# M617X.net
KiCad netlist of a schematic drawn in EAGLE
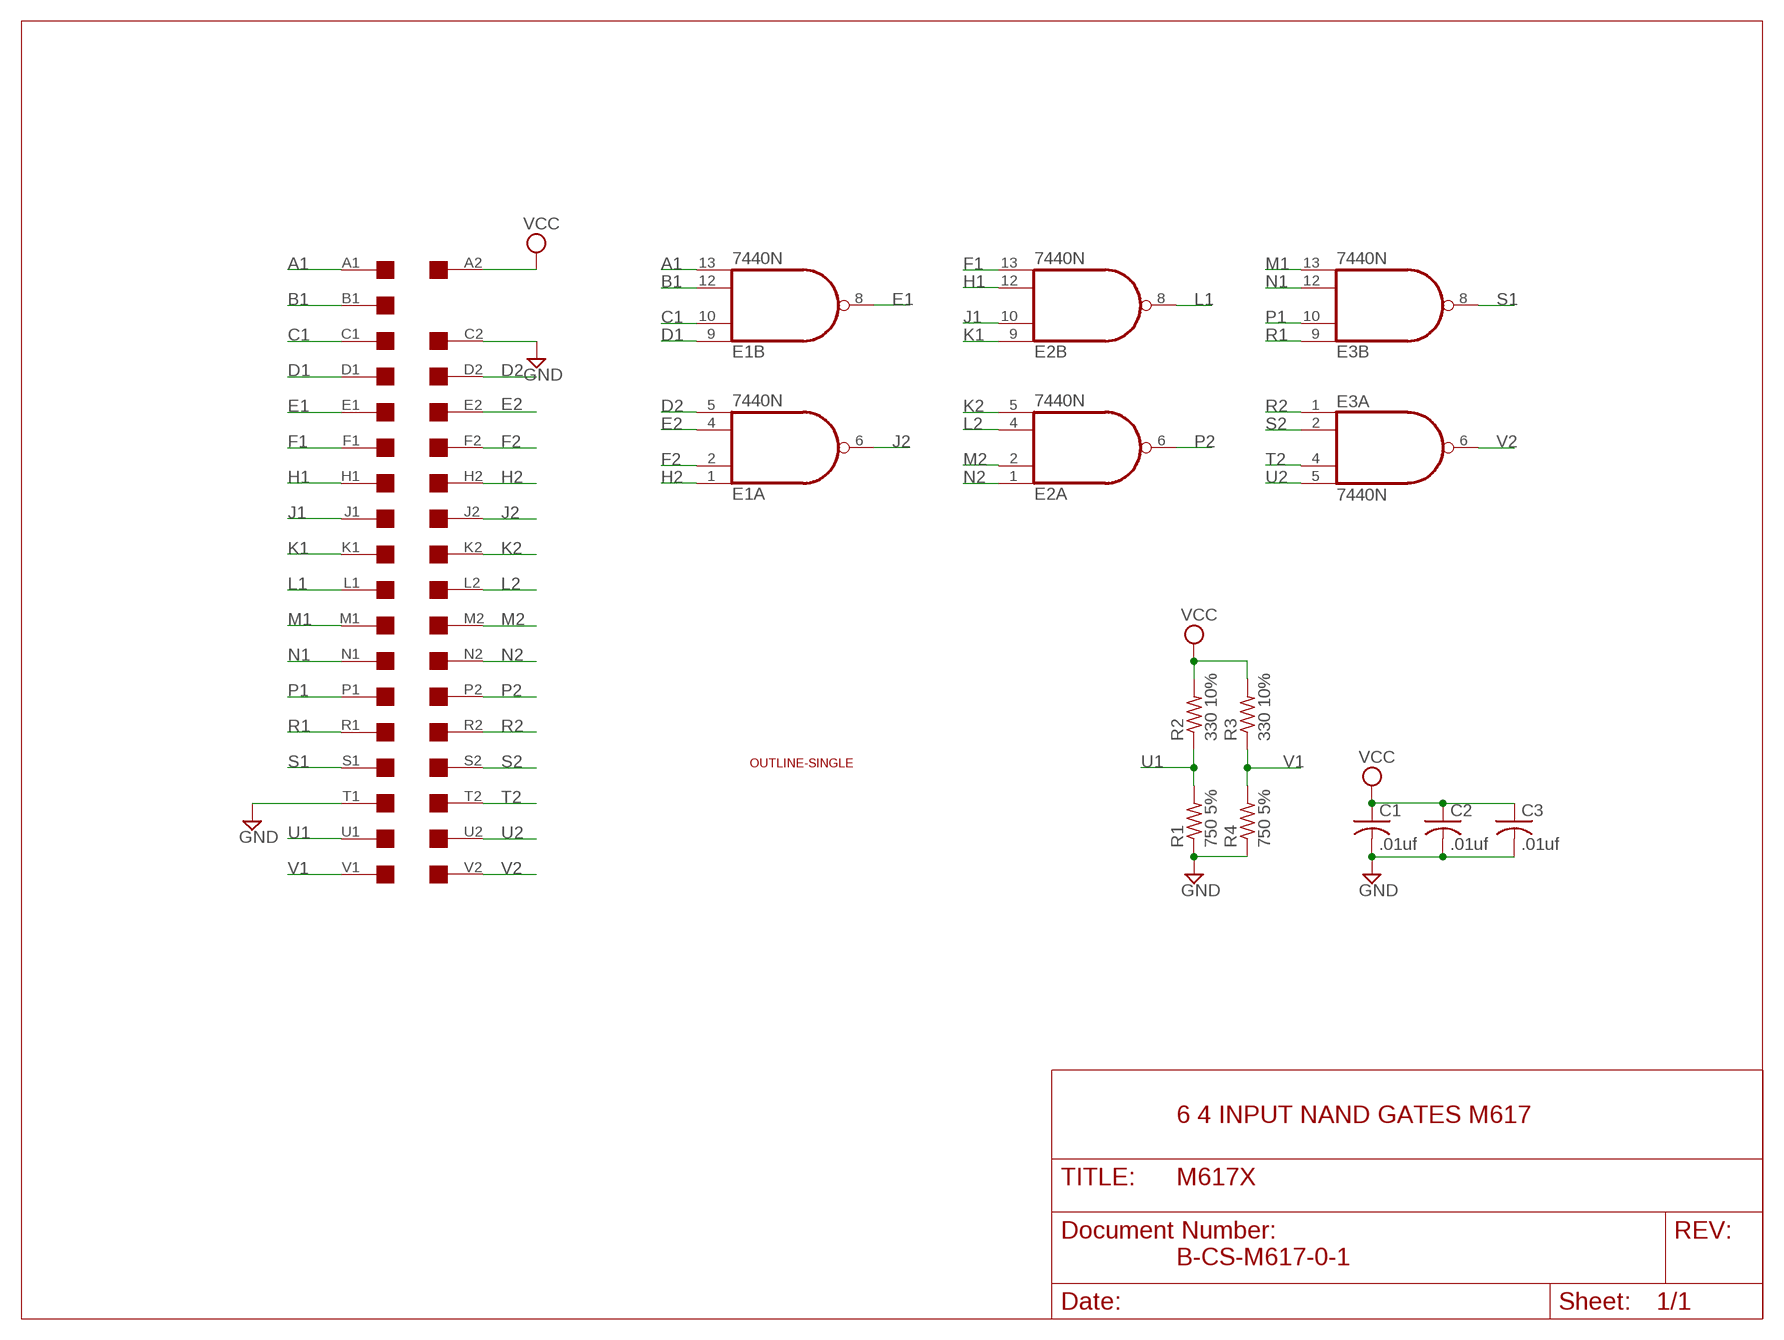
[diagram p0: schematic, sheet 1]

(export (version "E")
  (design (tool "Eeschema 10.0.6"))
  (components
    (comp (ref "C1")
      (value ".01uf")
      (footprint "eagle-import:C050-025X075")
      (libsource (lib "eagle-import") (part "C-US050-025X075"))
    )
    (comp (ref "C2")
      (value ".01uf")
      (footprint "eagle-import:C050-025X075")
      (libsource (lib "eagle-import") (part "C-US050-025X075"))
    )
    (comp (ref "C3")
      (value ".01uf")
      (footprint "eagle-import:C050-025X075")
      (libsource (lib "eagle-import") (part "C-US050-025X075"))
    )
    (comp (ref "E1")
      (value "7440N")
      (footprint "eagle-import:DIL14")
      (libsource (lib "eagle-import") (part "7420NS"))
    )
    (comp (ref "E2")
      (value "7440N")
      (footprint "eagle-import:DIL14")
      (libsource (lib "eagle-import") (part "7420NS"))
    )
    (comp (ref "E3")
      (value "7440N")
      (footprint "eagle-import:DIL14")
      (libsource (lib "eagle-import") (part "7420NS"))
    )
    (comp (ref "R1")
      (value "750 5%")
      (footprint "eagle-import:0207_10")
      (libsource (lib "eagle-import") (part "R-US_0207/10"))
    )
    (comp (ref "R2")
      (value "330 10%")
      (footprint "eagle-import:0207_10")
      (libsource (lib "eagle-import") (part "R-US_0207/10"))
    )
    (comp (ref "R3")
      (value "330 10%")
      (footprint "eagle-import:0207_10")
      (libsource (lib "eagle-import") (part "R-US_0207/10"))
    )
    (comp (ref "R4")
      (value "750 5%")
      (footprint "eagle-import:0207_10")
      (libsource (lib "eagle-import") (part "R-US_0207/10"))
    )
    (comp (ref "U$1")
      (value "SINGLE")
      (footprint "eagle-import:EDGE-CON2")
      (libsource (lib "eagle-import") (part "SINGLE"))
    )
    (comp (ref "U$4")
      (value "OUTLINE-SINGLE")
      (footprint "eagle-import:SINGLE")
      (libsource (lib "eagle-import") (part "OUTLINE-SINGLE"))
    )
  )
  (nets
    (net (code "1") (name "/A1") (class "Default")
      (node (ref "E1") (pin "13") (pinfunction "I3_13") (pintype "input"))
      (node (ref "U$1") (pin "A1") (pinfunction "1_A1") (pintype "bidirectional"))
    )
    (net (code "2") (name "/B1") (class "Default")
      (node (ref "E1") (pin "12") (pinfunction "I2_12") (pintype "input"))
      (node (ref "U$1") (pin "B1") (pinfunction "1_B1") (pintype "bidirectional"))
    )
    (net (code "3") (name "/C1") (class "Default")
      (node (ref "E1") (pin "10") (pinfunction "I1_10") (pintype "input"))
      (node (ref "U$1") (pin "C1") (pinfunction "1_C1") (pintype "bidirectional"))
    )
    (net (code "4") (name "/D1") (class "Default")
      (node (ref "E1") (pin "9") (pinfunction "I0_9") (pintype "input"))
      (node (ref "U$1") (pin "D1") (pinfunction "1_D1") (pintype "bidirectional"))
    )
    (net (code "5") (name "/D2") (class "Default")
      (node (ref "E1") (pin "5") (pinfunction "I3_5") (pintype "input"))
      (node (ref "U$1") (pin "D2") (pinfunction "1_D2") (pintype "bidirectional"))
    )
    (net (code "6") (name "/E1") (class "Default")
      (node (ref "E1") (pin "8") (pinfunction "O_8") (pintype "output"))
      (node (ref "U$1") (pin "E1") (pinfunction "1_E1") (pintype "bidirectional"))
    )
    (net (code "7") (name "/E2") (class "Default")
      (node (ref "E1") (pin "4") (pinfunction "I2_4") (pintype "input"))
      (node (ref "U$1") (pin "E2") (pinfunction "1_E2") (pintype "bidirectional"))
    )
    (net (code "8") (name "/F1") (class "Default")
      (node (ref "E2") (pin "13") (pinfunction "I3_13") (pintype "input"))
      (node (ref "U$1") (pin "F1") (pinfunction "1_F1") (pintype "bidirectional"))
    )
    (net (code "9") (name "/F2") (class "Default")
      (node (ref "E1") (pin "2") (pinfunction "I1_2") (pintype "input"))
      (node (ref "U$1") (pin "F2") (pinfunction "1_F2") (pintype "bidirectional"))
    )
    (net (code "10") (name "/H1") (class "Default")
      (node (ref "E2") (pin "12") (pinfunction "I2_12") (pintype "input"))
      (node (ref "U$1") (pin "H1") (pinfunction "1_H1") (pintype "bidirectional"))
    )
    (net (code "11") (name "/H2") (class "Default")
      (node (ref "E1") (pin "1") (pinfunction "I0_1") (pintype "input"))
      (node (ref "U$1") (pin "H2") (pinfunction "1_H2") (pintype "bidirectional"))
    )
    (net (code "12") (name "/J1") (class "Default")
      (node (ref "E2") (pin "10") (pinfunction "I1_10") (pintype "input"))
      (node (ref "U$1") (pin "J1") (pinfunction "1_J1") (pintype "bidirectional"))
    )
    (net (code "13") (name "/J2") (class "Default")
      (node (ref "E1") (pin "6") (pinfunction "O_6") (pintype "output"))
      (node (ref "U$1") (pin "J2") (pinfunction "1_J2") (pintype "bidirectional"))
    )
    (net (code "14") (name "/K1") (class "Default")
      (node (ref "E2") (pin "9") (pinfunction "I0_9") (pintype "input"))
      (node (ref "U$1") (pin "K1") (pinfunction "1_K1") (pintype "bidirectional"))
    )
    (net (code "15") (name "/K2") (class "Default")
      (node (ref "E2") (pin "5") (pinfunction "I3_5") (pintype "input"))
      (node (ref "U$1") (pin "K2") (pinfunction "1_K2") (pintype "bidirectional"))
    )
    (net (code "16") (name "/L1") (class "Default")
      (node (ref "E2") (pin "8") (pinfunction "O_8") (pintype "output"))
      (node (ref "U$1") (pin "L1") (pinfunction "1_L1") (pintype "bidirectional"))
    )
    (net (code "17") (name "/L2") (class "Default")
      (node (ref "E2") (pin "4") (pinfunction "I2_4") (pintype "input"))
      (node (ref "U$1") (pin "L2") (pinfunction "1_L2") (pintype "bidirectional"))
    )
    (net (code "18") (name "/M1") (class "Default")
      (node (ref "E3") (pin "13") (pinfunction "I3_13") (pintype "input"))
      (node (ref "U$1") (pin "M1") (pinfunction "1_M1") (pintype "bidirectional"))
    )
    (net (code "19") (name "/M2") (class "Default")
      (node (ref "E2") (pin "2") (pinfunction "I1_2") (pintype "input"))
      (node (ref "U$1") (pin "M2") (pinfunction "1_M2") (pintype "bidirectional"))
    )
    (net (code "20") (name "/N1") (class "Default")
      (node (ref "E3") (pin "12") (pinfunction "I2_12") (pintype "input"))
      (node (ref "U$1") (pin "N1") (pinfunction "1_N1") (pintype "bidirectional"))
    )
    (net (code "21") (name "/N2") (class "Default")
      (node (ref "E2") (pin "1") (pinfunction "I0_1") (pintype "input"))
      (node (ref "U$1") (pin "N2") (pinfunction "1_N2") (pintype "bidirectional"))
    )
    (net (code "22") (name "/P1") (class "Default")
      (node (ref "E3") (pin "10") (pinfunction "I1_10") (pintype "input"))
      (node (ref "U$1") (pin "P1") (pinfunction "1_P1") (pintype "bidirectional"))
    )
    (net (code "23") (name "/P2") (class "Default")
      (node (ref "E2") (pin "6") (pinfunction "O_6") (pintype "output"))
      (node (ref "U$1") (pin "P2") (pinfunction "1_P2") (pintype "bidirectional"))
    )
    (net (code "24") (name "/R1") (class "Default")
      (node (ref "E3") (pin "9") (pinfunction "I0_9") (pintype "input"))
      (node (ref "U$1") (pin "R1") (pinfunction "1_R1") (pintype "bidirectional"))
    )
    (net (code "25") (name "/R2") (class "Default")
      (node (ref "E3") (pin "1") (pinfunction "I0_1") (pintype "input"))
      (node (ref "U$1") (pin "R2") (pinfunction "1_R2") (pintype "bidirectional"))
    )
    (net (code "26") (name "/S1") (class "Default")
      (node (ref "E3") (pin "8") (pinfunction "O_8") (pintype "output"))
      (node (ref "U$1") (pin "S1") (pinfunction "1_S1") (pintype "bidirectional"))
    )
    (net (code "27") (name "/S2") (class "Default")
      (node (ref "E3") (pin "2") (pinfunction "I1_2") (pintype "input"))
      (node (ref "U$1") (pin "S2") (pinfunction "1_S2") (pintype "bidirectional"))
    )
    (net (code "28") (name "/T2") (class "Default")
      (node (ref "E3") (pin "4") (pinfunction "I2_4") (pintype "input"))
      (node (ref "U$1") (pin "T2") (pinfunction "1_T2") (pintype "bidirectional"))
    )
    (net (code "29") (name "/U1") (class "Default")
      (node (ref "R1") (pin "2") (pinfunction "2_2") (pintype "passive"))
      (node (ref "R2") (pin "1") (pinfunction "1_1") (pintype "passive"))
      (node (ref "U$1") (pin "U1") (pinfunction "1_U1") (pintype "bidirectional"))
    )
    (net (code "30") (name "/U2") (class "Default")
      (node (ref "E3") (pin "5") (pinfunction "I3_5") (pintype "input"))
      (node (ref "U$1") (pin "U2") (pinfunction "1_U2") (pintype "bidirectional"))
    )
    (net (code "31") (name "/V1") (class "Default")
      (node (ref "R3") (pin "1") (pinfunction "1_1") (pintype "passive"))
      (node (ref "R4") (pin "2") (pinfunction "2_2") (pintype "passive"))
      (node (ref "U$1") (pin "V1") (pinfunction "1_V1") (pintype "bidirectional"))
    )
    (net (code "32") (name "/V2") (class "Default")
      (node (ref "E3") (pin "6") (pinfunction "O_6") (pintype "output"))
      (node (ref "U$1") (pin "V2") (pinfunction "1_V2") (pintype "bidirectional"))
    )
    (net (code "33") (name "GND") (class "Default")
      (node (ref "C1") (pin "2") (pinfunction "2_2") (pintype "passive"))
      (node (ref "C2") (pin "2") (pinfunction "2_2") (pintype "passive"))
      (node (ref "C3") (pin "2") (pinfunction "2_2") (pintype "passive"))
      (node (ref "R1") (pin "1") (pinfunction "1_1") (pintype "passive"))
      (node (ref "R4") (pin "1") (pinfunction "1_1") (pintype "passive"))
      (node (ref "U$1") (pin "C2") (pinfunction "1_C2") (pintype "bidirectional"))
      (node (ref "U$1") (pin "T1") (pinfunction "1_T1") (pintype "bidirectional"))
    )
    (net (code "34") (name "VCC") (class "Default")
      (node (ref "C1") (pin "1") (pinfunction "1_1") (pintype "passive"))
      (node (ref "C2") (pin "1") (pinfunction "1_1") (pintype "passive"))
      (node (ref "C3") (pin "1") (pinfunction "1_1") (pintype "passive"))
      (node (ref "R2") (pin "2") (pinfunction "2_2") (pintype "passive"))
      (node (ref "R3") (pin "2") (pinfunction "2_2") (pintype "passive"))
      (node (ref "U$1") (pin "A2") (pinfunction "1_A2") (pintype "bidirectional"))
    )
  )
)
